# 05-RTC.net
KiCad netlist of a schematic drawn in Altium Designer
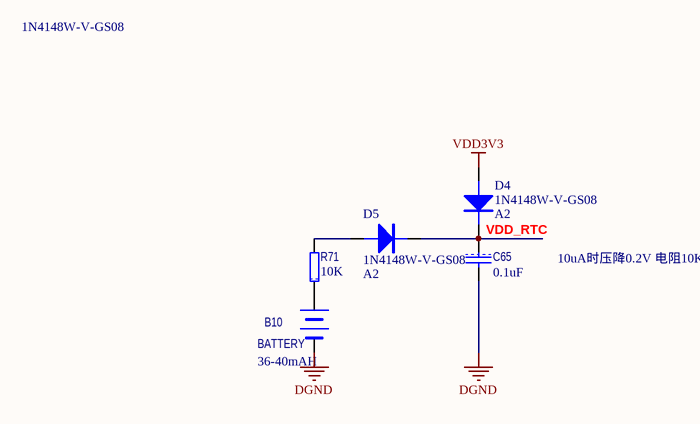
[diagram p0: 05-RTC.SchDoc]

(export (version "E")
  (design (tool "Eeschema 10.0.6"))
  (components
    (comp (ref "B10")
      (value "BATTERY")
      (footprint "BR2032-1GV")
      (description "插针 电池座")
      (fields (field (name "VOLUME") "36-40mAH"))
      (libsource (lib "*") (part "BATTERY"))
    )
    (comp (ref "C65")
      (value "0.1uF")
      (footprint "1608[0603]C")
      (description "多层陶瓷电容器MLCC - SMD/SMT 0603 0.1uF 50volts X7R 10%")
      (fields (field (name "MANUFACTURER") "TDK") (field (name "MANUFACTURER PART NUMBER") "C1608X7R1H104K"))
      (libsource (lib "*") (part "CAP"))
    )
    (comp (ref "D4")
      (value "1N4148W-V-GS08")
      (footprint "SOD123")
      (description "二极管 - 通用，功率，开关 100V Io/150mA")
      (fields (field (name "MANUFACTURER") "Vishay Semiconductors") (field (name "ALTIUM_VALUE") "A2"))
      (libsource (lib "IN4148") (part "1N4148W"))
    )
    (comp (ref "D5")
      (value "1N4148W-V-GS08")
      (footprint "SOD123")
      (description "二极管 - 通用，功率，开关 100V Io/150mA")
      (fields (field (name "MANUFACTURER") "Vishay Semiconductors") (field (name "ALTIUM_VALUE") "A2"))
      (libsource (lib "IN4148") (part "1N4148W"))
    )
    (comp (ref "R71")
      (value "10K")
      (footprint "1608[0603]R")
      (description "厚膜电阻器 - SMD 1/10watt 10Kohms 1%")
      (fields
        (field (name "MANUFACTURER") "Vishay / Dale")
        (field (name "MANUFACTURER PART NUMBER") "CRCW060310K0FKEA")
      )
      (libsource (lib "10K 1%") (part "RES"))
    )
  )
  (nets
    (net (code "1") (name "/VDD_RTC") (class "Default")
      (node (ref "C65") (pin "1") (pinfunction "1_1") (pintype "passive"))
      (node (ref "D4") (pin "2") (pinfunction "K_2") (pintype "passive"))
      (node (ref "D5") (pin "2") (pinfunction "K_2") (pintype "passive"))
    )
    (net (code "2") (name "DGND") (class "Default")
      (node (ref "B10") (pin "2") (pintype "passive"))
      (node (ref "C65") (pin "2") (pinfunction "2_2") (pintype "passive"))
    )
    (net (code "3") (name "Net-(B10-Pad1)") (class "Default")
      (node (ref "B10") (pin "1") (pintype "passive"))
      (node (ref "R71") (pin "1") (pinfunction "1_1") (pintype "passive"))
    )
    (net (code "4") (name "Net-(D5-A)") (class "Default")
      (node (ref "D5") (pin "1") (pinfunction "A_1") (pintype "passive"))
      (node (ref "R71") (pin "2") (pinfunction "2_2") (pintype "passive"))
    )
    (net (code "5") (name "VDD3V3") (class "Default")
      (node (ref "D4") (pin "1") (pinfunction "A_1") (pintype "passive"))
    )
  )
)
